# Connectors_GPIOs.net
KiCad netlist of a schematic drawn in Altium Designer
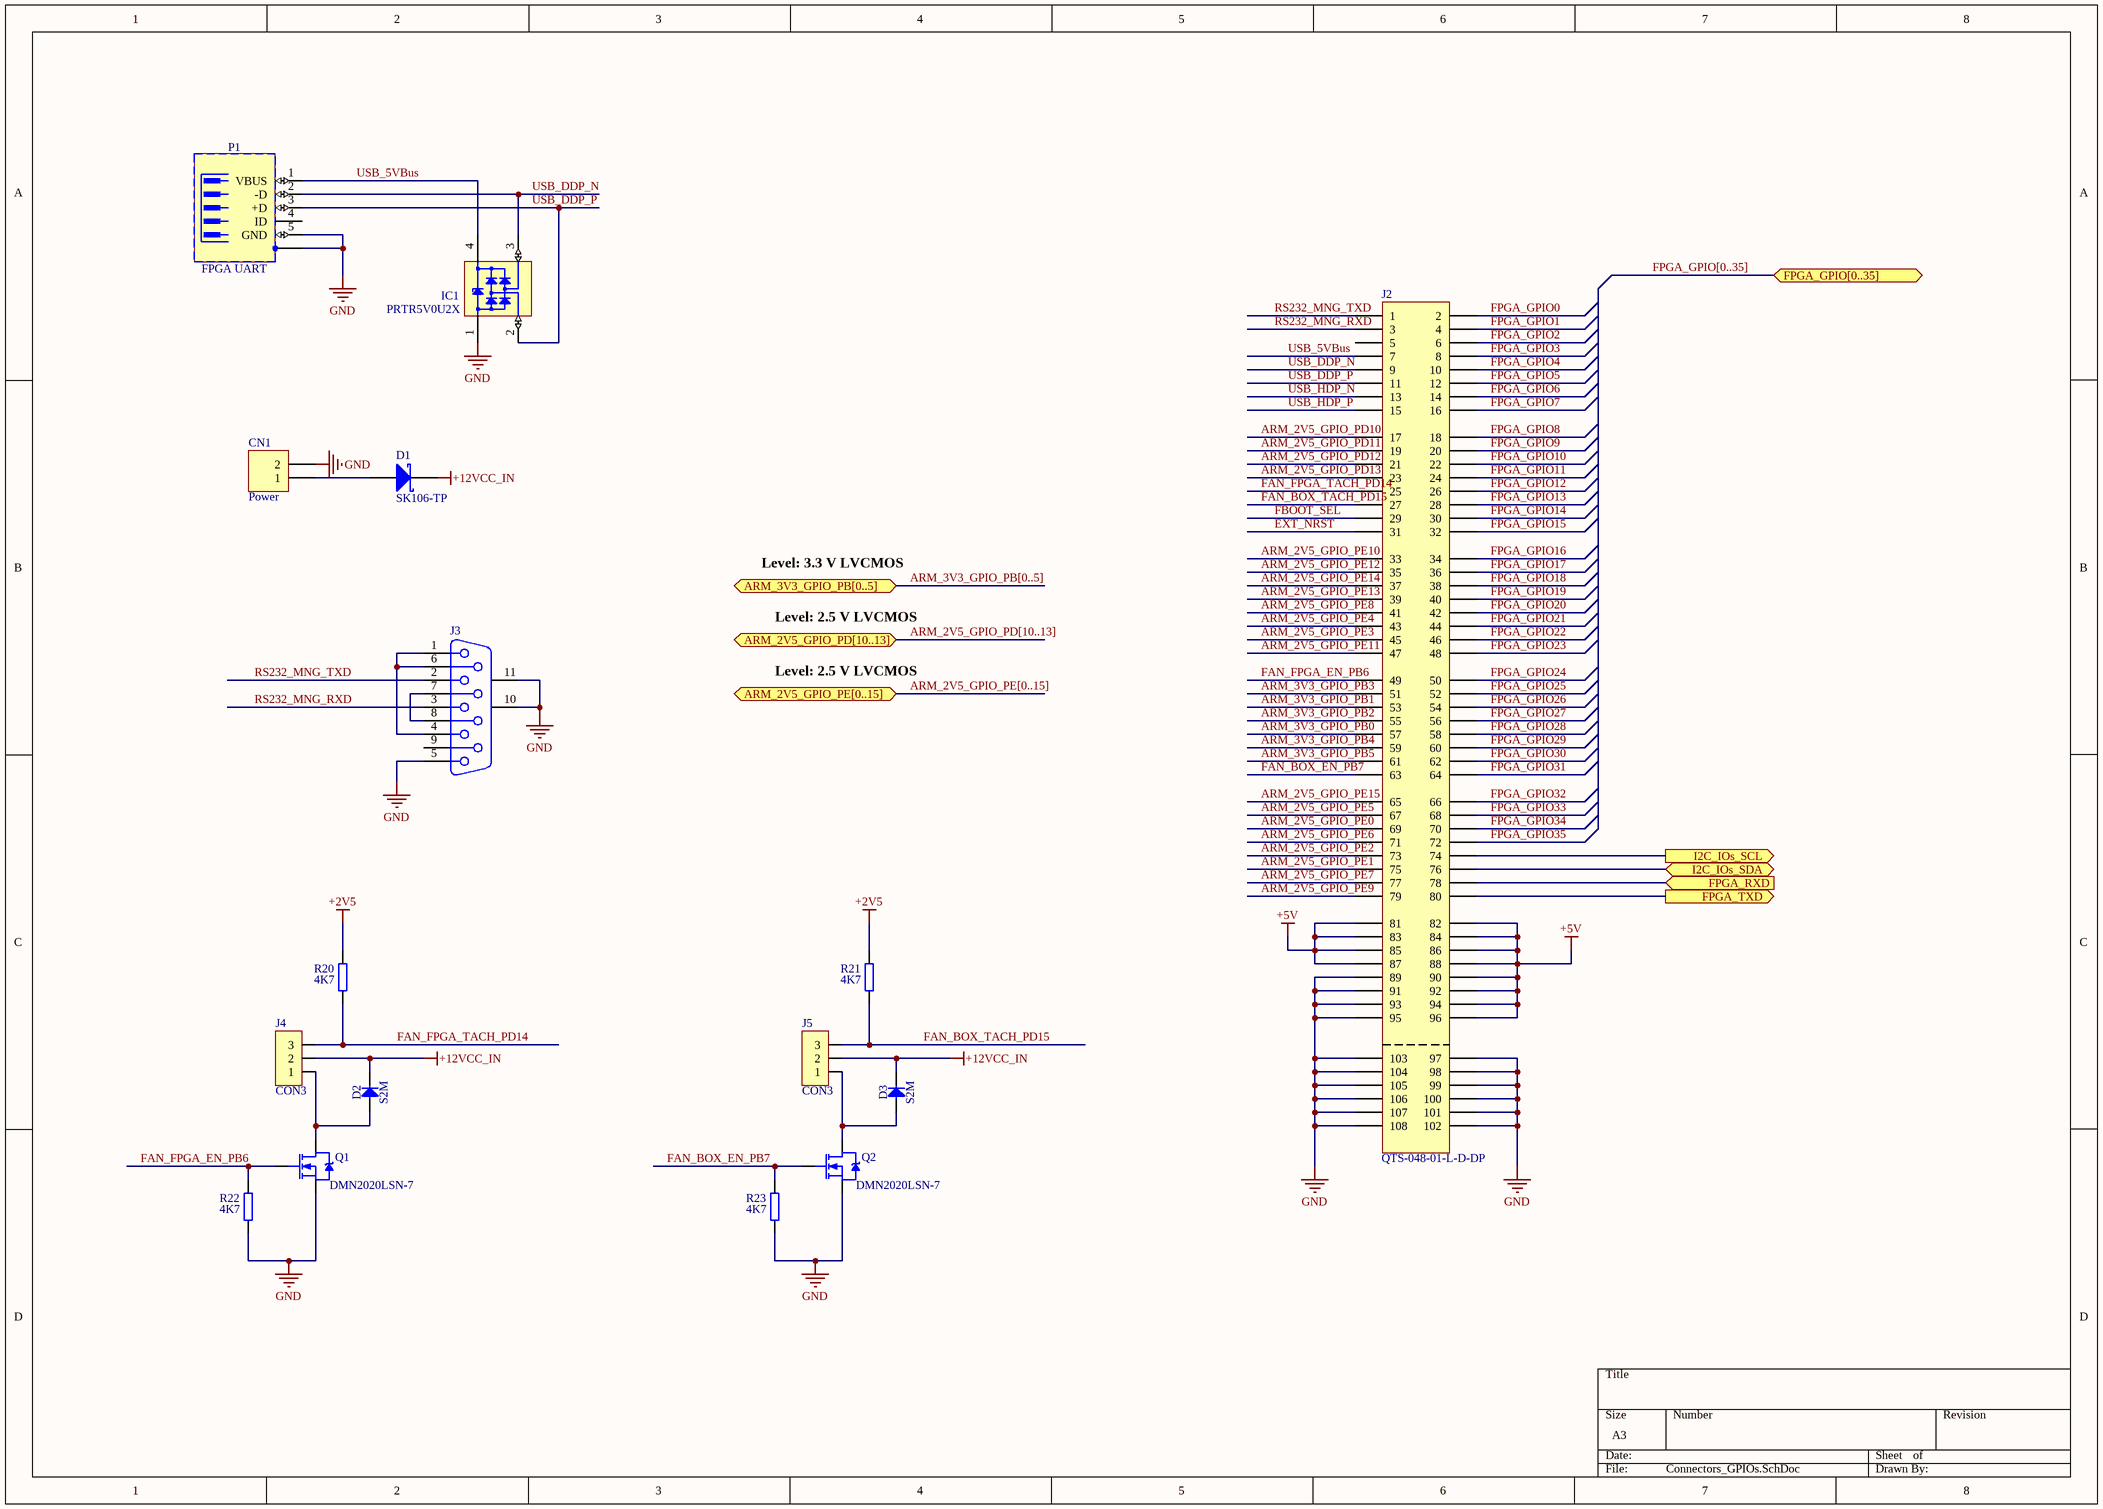
[diagram p0: Connectors_GPIOs.SchDoc]

(export (version "E")
  (design (tool "Eeschema 10.0.6"))
  (components
    (comp (ref "CN1")
      (value "Power")
      (description "Header, 2-Pin")
      (fields (field (name "PUBLISHER") "Altium Limited"))
      (libsource (lib "Miscellaneous Connectors") (part "Header 2"))
    )
    (comp (ref "D1")
      (value "SK106-TP")
      (footprint "DIOM7959X262N")
      (description "Schottky Diode 10A 60V")
      (libsource (lib "wr_switch") (part "SK106-TP"))
    )
    (comp (ref "D2")
      (value "S2M")
      (footprint "DIOM5336X265N")
      (description "Diode")
      (fields
        (field (name "VOLTAGE") "1000V")
        (field (name "POWER") "2A")
        (field (name "AUTHOR") "CERN DEM JLC")
      )
      (libsource (lib "ICs And Semiconductors") (part "Diode"))
    )
    (comp (ref "D3")
      (value "S2M")
      (footprint "DIOM5336X265N")
      (description "Diode")
      (fields
        (field (name "VOLTAGE") "1000V")
        (field (name "POWER") "2A")
        (field (name "AUTHOR") "CERN DEM JLC")
      )
      (libsource (lib "ICs And Semiconductors") (part "Diode"))
    )
    (comp (ref "IC1")
      (value "PRTR5V0U2X")
      (footprint "SOT190P230X110-4N")
      (description "Ultra Low Capacitance Double Rail-to-Rail ESD Protection Diode")
      (fields
        (field (name "VOLTAGE") "5.5V")
        (field (name "MANUFACTURER") "PHILIPS NXP")
        (field (name "AUTHOR") "CERN DEM JLC")
      )
      (libsource (lib "wr_switch") (part "PRTR5V0U2X"))
    )
    (comp (ref "J2")
      (value "QTS-048-01-L-D-DP")
      (footprint "QTS-048-XX-X-D-DP-A")
      (description "High Speed Ground Plane Header")
      (libsource (lib "wr_switch") (part "QTS-048-01-L-D-DP"))
    )
    (comp (ref "J3")
      (value "D Connector 9")
      (footprint "DSUB1.385-2H9")
      (description "Receptacle Assembly, 9 Position, Right Angle")
      (fields (field (name "PUBLISHER") "Altium Limited"))
      (libsource (lib "Miscellaneous Connectors") (part "D Connector 9"))
    )
    (comp (ref "J4")
      (value "CON3")
      (footprint "HDR1X3")
      (description "Connector")
      (libsource (lib "LIBRARY_SCH") (part "CON3"))
    )
    (comp (ref "J5")
      (value "CON3")
      (footprint "HDR1X3")
      (description "Connector")
      (libsource (lib "LIBRARY_SCH") (part "CON3"))
    )
    (comp (ref "P1")
      (value "FPGA UART")
      (footprint "TYCO_1734035-1")
      (description "5 Pin + 1 Shield USB Receptacle")
      (fields
        (field (name "PART NUMBER") "TYCO_1734035-1")
        (field (name "MANUFACTURER") "TYCO ELECTRONICS")
        (field (name "AUTHOR") "CERN DEM JLC")
      )
      (libsource (lib "Connectors") (part "Connector USB 5 Pin + 1Shield"))
    )
    (comp (ref "Q1")
      (value "DMN2020LSN-7")
      (footprint "SC-59-3")
      (description "N-Channel Power MOSFET")
      (fields (field (name "MANUFACTURER") "Diodes Inc.") (field (name "PUBLISHER") "Altium Limited"))
      (libsource (lib "wr_switch") (part "NMOS-2"))
    )
    (comp (ref "Q2")
      (value "DMN2020LSN-7")
      (footprint "SC-59-3")
      (description "N-Channel Power MOSFET")
      (fields (field (name "MANUFACTURER") "Diodes Inc.") (field (name "PUBLISHER") "Altium Limited"))
      (libsource (lib "wr_switch") (part "NMOS-2"))
    )
    (comp (ref "R20")
      (value "4K7")
      (footprint "0603")
      (description "SMD Resistor")
      (fields (field (name "TOLERANCE") "±1%"))
      (libsource (lib "wr_switch") (part "RES_SMD"))
    )
    (comp (ref "R21")
      (value "4K7")
      (footprint "0603")
      (description "SMD Resistor")
      (fields (field (name "TOLERANCE") "±1%"))
      (libsource (lib "wr_switch") (part "RES_SMD"))
    )
    (comp (ref "R22")
      (value "4K7")
      (footprint "0603")
      (description "SMD Resistor")
      (fields (field (name "TOLERANCE") "±1%"))
      (libsource (lib "wr_switch") (part "RES_SMD"))
    )
    (comp (ref "R23")
      (value "4K7")
      (footprint "0603")
      (description "SMD Resistor")
      (fields (field (name "TOLERANCE") "±1%"))
      (libsource (lib "wr_switch") (part "RES_SMD"))
    )
  )
  (nets
    (net (code "1") (name "+2V5") (class "Default")
      (node (ref "R20") (pin "1") (pinfunction "1_1") (pintype "passive"))
      (node (ref "R21") (pin "1") (pinfunction "1_1") (pintype "passive"))
    )
    (net (code "2") (name "+5V") (class "Default")
      (node (ref "J2") (pin "81") (pinfunction "81_81") (pintype "passive"))
      (node (ref "J2") (pin "82") (pinfunction "82_82") (pintype "passive"))
      (node (ref "J2") (pin "83") (pinfunction "83_83") (pintype "passive"))
      (node (ref "J2") (pin "84") (pinfunction "84_84") (pintype "passive"))
      (node (ref "J2") (pin "85") (pinfunction "85_85") (pintype "passive"))
      (node (ref "J2") (pin "86") (pinfunction "86_86") (pintype "passive"))
      (node (ref "J2") (pin "87") (pinfunction "87_87") (pintype "passive"))
      (node (ref "J2") (pin "88") (pinfunction "88_88") (pintype "passive"))
      (node (ref "J2") (pin "90") (pinfunction "90_90") (pintype "passive"))
      (node (ref "J2") (pin "92") (pinfunction "92_92") (pintype "passive"))
      (node (ref "J2") (pin "94") (pinfunction "94_94") (pintype "passive"))
      (node (ref "J2") (pin "96") (pinfunction "96_96") (pintype "passive"))
    )
    (net (code "3") (name "+12VCC_IN") (class "Default")
      (node (ref "D1") (pin "2") (pinfunction "K_2") (pintype "passive"))
      (node (ref "D2") (pin "1") (pinfunction "C_1") (pintype "passive"))
      (node (ref "D3") (pin "1") (pinfunction "C_1") (pintype "passive"))
      (node (ref "J4") (pin "2") (pinfunction "2_2") (pintype "passive"))
      (node (ref "J5") (pin "2") (pinfunction "2_2") (pintype "passive"))
    )
    (net (code "4") (name "/ARM_2V5_GPIO_PD10") (class "Default")
      (node (ref "J2") (pin "17") (pinfunction "17_17") (pintype "passive"))
    )
    (net (code "5") (name "/ARM_2V5_GPIO_PD11") (class "Default")
      (node (ref "J2") (pin "19") (pinfunction "19_19") (pintype "passive"))
    )
    (net (code "6") (name "/ARM_2V5_GPIO_PD12") (class "Default")
      (node (ref "J2") (pin "21") (pinfunction "21_21") (pintype "passive"))
    )
    (net (code "7") (name "/ARM_2V5_GPIO_PD13") (class "Default")
      (node (ref "J2") (pin "23") (pinfunction "23_23") (pintype "passive"))
    )
    (net (code "9") (name "/ARM_2V5_GPIO_PE0") (class "Default")
      (node (ref "J2") (pin "69") (pinfunction "69_69") (pintype "passive"))
    )
    (net (code "10") (name "/ARM_2V5_GPIO_PE1") (class "Default")
      (node (ref "J2") (pin "75") (pinfunction "75_75") (pintype "passive"))
    )
    (net (code "11") (name "/ARM_2V5_GPIO_PE2") (class "Default")
      (node (ref "J2") (pin "73") (pinfunction "73_73") (pintype "passive"))
    )
    (net (code "12") (name "/ARM_2V5_GPIO_PE3") (class "Default")
      (node (ref "J2") (pin "45") (pinfunction "45_45") (pintype "passive"))
    )
    (net (code "13") (name "/ARM_2V5_GPIO_PE4") (class "Default")
      (node (ref "J2") (pin "43") (pinfunction "43_43") (pintype "passive"))
    )
    (net (code "14") (name "/ARM_2V5_GPIO_PE5") (class "Default")
      (node (ref "J2") (pin "67") (pinfunction "67_67") (pintype "passive"))
    )
    (net (code "15") (name "/ARM_2V5_GPIO_PE6") (class "Default")
      (node (ref "J2") (pin "71") (pinfunction "71_71") (pintype "passive"))
    )
    (net (code "16") (name "/ARM_2V5_GPIO_PE7") (class "Default")
      (node (ref "J2") (pin "77") (pinfunction "77_77") (pintype "passive"))
    )
    (net (code "17") (name "/ARM_2V5_GPIO_PE8") (class "Default")
      (node (ref "J2") (pin "41") (pinfunction "41_41") (pintype "passive"))
    )
    (net (code "18") (name "/ARM_2V5_GPIO_PE9") (class "Default")
      (node (ref "J2") (pin "79") (pinfunction "79_79") (pintype "passive"))
    )
    (net (code "19") (name "/ARM_2V5_GPIO_PE10") (class "Default")
      (node (ref "J2") (pin "33") (pinfunction "33_33") (pintype "passive"))
    )
    (net (code "20") (name "/ARM_2V5_GPIO_PE11") (class "Default")
      (node (ref "J2") (pin "47") (pinfunction "47_47") (pintype "passive"))
    )
    (net (code "21") (name "/ARM_2V5_GPIO_PE12") (class "Default")
      (node (ref "J2") (pin "35") (pinfunction "35_35") (pintype "passive"))
    )
    (net (code "22") (name "/ARM_2V5_GPIO_PE13") (class "Default")
      (node (ref "J2") (pin "39") (pinfunction "39_39") (pintype "passive"))
    )
    (net (code "23") (name "/ARM_2V5_GPIO_PE14") (class "Default")
      (node (ref "J2") (pin "37") (pinfunction "37_37") (pintype "passive"))
    )
    (net (code "24") (name "/ARM_2V5_GPIO_PE15") (class "Default")
      (node (ref "J2") (pin "65") (pinfunction "65_65") (pintype "passive"))
    )
    (net (code "26") (name "/ARM_3V3_GPIO_PB0") (class "Default")
      (node (ref "J2") (pin "57") (pinfunction "57_57") (pintype "passive"))
    )
    (net (code "27") (name "/ARM_3V3_GPIO_PB1") (class "Default")
      (node (ref "J2") (pin "53") (pinfunction "53_53") (pintype "passive"))
    )
    (net (code "28") (name "/ARM_3V3_GPIO_PB2") (class "Default")
      (node (ref "J2") (pin "55") (pinfunction "55_55") (pintype "passive"))
    )
    (net (code "29") (name "/ARM_3V3_GPIO_PB3") (class "Default")
      (node (ref "J2") (pin "51") (pinfunction "51_51") (pintype "passive"))
    )
    (net (code "30") (name "/ARM_3V3_GPIO_PB4") (class "Default")
      (node (ref "J2") (pin "59") (pinfunction "59_59") (pintype "passive"))
    )
    (net (code "31") (name "/ARM_3V3_GPIO_PB5") (class "Default")
      (node (ref "J2") (pin "61") (pinfunction "61_61") (pintype "passive"))
    )
    (net (code "33") (name "/EXT_NRST") (class "Default")
      (node (ref "J2") (pin "31") (pinfunction "31_31") (pintype "passive"))
    )
    (net (code "34") (name "/FAN_BOX_EN_PB7") (class "Default")
      (node (ref "J2") (pin "63") (pinfunction "63_63") (pintype "passive"))
      (node (ref "Q2") (pin "1") (pinfunction "G_1") (pintype "passive"))
      (node (ref "R23") (pin "1") (pinfunction "1_1") (pintype "passive"))
    )
    (net (code "35") (name "/FAN_BOX_TACH_PD15") (class "Default")
      (node (ref "J2") (pin "27") (pinfunction "27_27") (pintype "passive"))
      (node (ref "J5") (pin "3") (pinfunction "3_3") (pintype "passive"))
      (node (ref "R21") (pin "2") (pinfunction "2_2") (pintype "passive"))
    )
    (net (code "36") (name "/FAN_FPGA_EN_PB6") (class "Default")
      (node (ref "J2") (pin "49") (pinfunction "49_49") (pintype "passive"))
      (node (ref "Q1") (pin "1") (pinfunction "G_1") (pintype "passive"))
      (node (ref "R22") (pin "1") (pinfunction "1_1") (pintype "passive"))
    )
    (net (code "37") (name "/FAN_FPGA_TACH_PD14") (class "Default")
      (node (ref "J2") (pin "25") (pinfunction "25_25") (pintype "passive"))
      (node (ref "J4") (pin "3") (pinfunction "3_3") (pintype "passive"))
      (node (ref "R20") (pin "2") (pinfunction "2_2") (pintype "passive"))
    )
    (net (code "38") (name "/FBOOT_SEL") (class "Default")
      (node (ref "J2") (pin "29") (pinfunction "29_29") (pintype "passive"))
    )
    (net (code "39") (name "/FPGA_GPIO0") (class "Default")
      (node (ref "J2") (pin "2") (pinfunction "2_2") (pintype "passive"))
    )
    (net (code "40") (name "/FPGA_GPIO1") (class "Default")
      (node (ref "J2") (pin "4") (pinfunction "4_4") (pintype "passive"))
    )
    (net (code "41") (name "/FPGA_GPIO2") (class "Default")
      (node (ref "J2") (pin "6") (pinfunction "6_6") (pintype "passive"))
    )
    (net (code "42") (name "/FPGA_GPIO3") (class "Default")
      (node (ref "J2") (pin "8") (pinfunction "8_8") (pintype "passive"))
    )
    (net (code "43") (name "/FPGA_GPIO4") (class "Default")
      (node (ref "J2") (pin "10") (pinfunction "10_10") (pintype "passive"))
    )
    (net (code "44") (name "/FPGA_GPIO5") (class "Default")
      (node (ref "J2") (pin "12") (pinfunction "12_12") (pintype "passive"))
    )
    (net (code "45") (name "/FPGA_GPIO6") (class "Default")
      (node (ref "J2") (pin "14") (pinfunction "14_14") (pintype "passive"))
    )
    (net (code "46") (name "/FPGA_GPIO7") (class "Default")
      (node (ref "J2") (pin "16") (pinfunction "16_16") (pintype "passive"))
    )
    (net (code "47") (name "/FPGA_GPIO8") (class "Default")
      (node (ref "J2") (pin "18") (pinfunction "18_18") (pintype "passive"))
    )
    (net (code "48") (name "/FPGA_GPIO9") (class "Default")
      (node (ref "J2") (pin "20") (pinfunction "20_20") (pintype "passive"))
    )
    (net (code "49") (name "/FPGA_GPIO10") (class "Default")
      (node (ref "J2") (pin "22") (pinfunction "22_22") (pintype "passive"))
    )
    (net (code "50") (name "/FPGA_GPIO11") (class "Default")
      (node (ref "J2") (pin "24") (pinfunction "24_24") (pintype "passive"))
    )
    (net (code "51") (name "/FPGA_GPIO12") (class "Default")
      (node (ref "J2") (pin "26") (pinfunction "26_26") (pintype "passive"))
    )
    (net (code "52") (name "/FPGA_GPIO13") (class "Default")
      (node (ref "J2") (pin "28") (pinfunction "28_28") (pintype "passive"))
    )
    (net (code "53") (name "/FPGA_GPIO14") (class "Default")
      (node (ref "J2") (pin "30") (pinfunction "30_30") (pintype "passive"))
    )
    (net (code "54") (name "/FPGA_GPIO15") (class "Default")
      (node (ref "J2") (pin "32") (pinfunction "32_32") (pintype "passive"))
    )
    (net (code "55") (name "/FPGA_GPIO16") (class "Default")
      (node (ref "J2") (pin "34") (pinfunction "34_34") (pintype "passive"))
    )
    (net (code "56") (name "/FPGA_GPIO17") (class "Default")
      (node (ref "J2") (pin "36") (pinfunction "36_36") (pintype "passive"))
    )
    (net (code "57") (name "/FPGA_GPIO18") (class "Default")
      (node (ref "J2") (pin "38") (pinfunction "38_38") (pintype "passive"))
    )
    (net (code "58") (name "/FPGA_GPIO19") (class "Default")
      (node (ref "J2") (pin "40") (pinfunction "40_40") (pintype "passive"))
    )
    (net (code "59") (name "/FPGA_GPIO20") (class "Default")
      (node (ref "J2") (pin "42") (pinfunction "42_42") (pintype "passive"))
    )
    (net (code "60") (name "/FPGA_GPIO21") (class "Default")
      (node (ref "J2") (pin "44") (pinfunction "44_44") (pintype "passive"))
    )
    (net (code "61") (name "/FPGA_GPIO22") (class "Default")
      (node (ref "J2") (pin "46") (pinfunction "46_46") (pintype "passive"))
    )
    (net (code "62") (name "/FPGA_GPIO23") (class "Default")
      (node (ref "J2") (pin "48") (pinfunction "48_48") (pintype "passive"))
    )
    (net (code "63") (name "/FPGA_GPIO24") (class "Default")
      (node (ref "J2") (pin "50") (pinfunction "50_50") (pintype "passive"))
    )
    (net (code "64") (name "/FPGA_GPIO25") (class "Default")
      (node (ref "J2") (pin "52") (pinfunction "52_52") (pintype "passive"))
    )
    (net (code "65") (name "/FPGA_GPIO26") (class "Default")
      (node (ref "J2") (pin "54") (pinfunction "54_54") (pintype "passive"))
    )
    (net (code "66") (name "/FPGA_GPIO27") (class "Default")
      (node (ref "J2") (pin "56") (pinfunction "56_56") (pintype "passive"))
    )
    (net (code "67") (name "/FPGA_GPIO28") (class "Default")
      (node (ref "J2") (pin "58") (pinfunction "58_58") (pintype "passive"))
    )
    (net (code "68") (name "/FPGA_GPIO29") (class "Default")
      (node (ref "J2") (pin "60") (pinfunction "60_60") (pintype "passive"))
    )
    (net (code "69") (name "/FPGA_GPIO30") (class "Default")
      (node (ref "J2") (pin "62") (pinfunction "62_62") (pintype "passive"))
    )
    (net (code "70") (name "/FPGA_GPIO31") (class "Default")
      (node (ref "J2") (pin "64") (pinfunction "64_64") (pintype "passive"))
    )
    (net (code "71") (name "/FPGA_GPIO32") (class "Default")
      (node (ref "J2") (pin "66") (pinfunction "66_66") (pintype "passive"))
    )
    (net (code "72") (name "/FPGA_GPIO33") (class "Default")
      (node (ref "J2") (pin "68") (pinfunction "68_68") (pintype "passive"))
    )
    (net (code "73") (name "/FPGA_GPIO34") (class "Default")
      (node (ref "J2") (pin "70") (pinfunction "70_70") (pintype "passive"))
    )
    (net (code "74") (name "/FPGA_GPIO35") (class "Default")
      (node (ref "J2") (pin "72") (pinfunction "72_72") (pintype "passive"))
    )
    (net (code "76") (name "/FPGA_RXD") (class "Default")
      (node (ref "J2") (pin "78") (pinfunction "78_78") (pintype "passive"))
    )
    (net (code "77") (name "/FPGA_TXD") (class "Default")
      (node (ref "J2") (pin "80") (pinfunction "80_80") (pintype "passive"))
    )
    (net (code "78") (name "/I2C_IOs_SCL") (class "Default")
      (node (ref "J2") (pin "74") (pinfunction "74_74") (pintype "passive"))
    )
    (net (code "79") (name "/I2C_IOs_SDA") (class "Default")
      (node (ref "J2") (pin "76") (pinfunction "76_76") (pintype "passive"))
    )
    (net (code "80") (name "/RS232_MNG_RXD") (class "Default")
      (node (ref "J2") (pin "3") (pinfunction "3_3") (pintype "passive"))
      (node (ref "J3") (pin "3") (pinfunction "3_3") (pintype "passive"))
    )
    (net (code "81") (name "/RS232_MNG_TXD") (class "Default")
      (node (ref "J2") (pin "1") (pinfunction "1_1") (pintype "passive"))
      (node (ref "J3") (pin "2") (pinfunction "2_2") (pintype "passive"))
    )
    (net (code "82") (name "/USB_5VBus") (class "Default")
      (node (ref "IC1") (pin "4") (pinfunction "VCC_4") (pintype "power_in"))
      (node (ref "J2") (pin "7") (pinfunction "7_7") (pintype "passive"))
      (node (ref "P1") (pin "1") (pinfunction "VBUS_1") (pintype "bidirectional"))
    )
    (net (code "83") (name "/USB_DDP_N") (class "Default")
      (node (ref "IC1") (pin "3") (pinfunction "I/O2_3") (pintype "bidirectional"))
      (node (ref "J2") (pin "9") (pinfunction "9_9") (pintype "passive"))
      (node (ref "P1") (pin "2") (pinfunction "-D_2") (pintype "bidirectional"))
    )
    (net (code "84") (name "/USB_DDP_P") (class "Default")
      (node (ref "IC1") (pin "2") (pinfunction "I/O1_2") (pintype "bidirectional"))
      (node (ref "J2") (pin "11") (pinfunction "11_11") (pintype "passive"))
      (node (ref "P1") (pin "3") (pinfunction "+D_3") (pintype "bidirectional"))
    )
    (net (code "85") (name "/USB_HDP_N") (class "Default")
      (node (ref "J2") (pin "13") (pinfunction "13_13") (pintype "passive"))
    )
    (net (code "86") (name "/USB_HDP_P") (class "Default")
      (node (ref "J2") (pin "15") (pinfunction "15_15") (pintype "passive"))
    )
    (net (code "87") (name "GND") (class "Default")
      (node (ref "CN1") (pin "2") (pinfunction "2_2") (pintype "passive"))
      (node (ref "IC1") (pin "1") (pinfunction "GND_1") (pintype "power_in"))
      (node (ref "J2") (pin "100") (pinfunction "100_100") (pintype "passive"))
      (node (ref "J2") (pin "101") (pinfunction "101_101") (pintype "passive"))
      (node (ref "J2") (pin "102") (pinfunction "102_102") (pintype "passive"))
      (node (ref "J2") (pin "103") (pinfunction "103_103") (pintype "passive"))
      (node (ref "J2") (pin "104") (pinfunction "104_104") (pintype "passive"))
      (node (ref "J2") (pin "105") (pinfunction "105_105") (pintype "passive"))
      (node (ref "J2") (pin "106") (pinfunction "106_106") (pintype "passive"))
      (node (ref "J2") (pin "107") (pinfunction "107_107") (pintype "passive"))
      (node (ref "J2") (pin "108") (pinfunction "108_108") (pintype "passive"))
      (node (ref "J2") (pin "89") (pinfunction "89_89") (pintype "passive"))
      (node (ref "J2") (pin "91") (pinfunction "91_91") (pintype "passive"))
      (node (ref "J2") (pin "93") (pinfunction "93_93") (pintype "passive"))
      (node (ref "J2") (pin "95") (pinfunction "95_95") (pintype "passive"))
      (node (ref "J2") (pin "97") (pinfunction "97_97") (pintype "passive"))
      (node (ref "J2") (pin "98") (pinfunction "98_98") (pintype "passive"))
      (node (ref "J2") (pin "99") (pinfunction "99_99") (pintype "passive"))
      (node (ref "J3") (pin "10") (pinfunction "MH1_10") (pintype "passive"))
      (node (ref "J3") (pin "11") (pinfunction "MH2_11") (pintype "passive"))
      (node (ref "J3") (pin "5") (pinfunction "5_5") (pintype "passive"))
      (node (ref "P1") (pin "5") (pinfunction "GND_5") (pintype "bidirectional"))
      (node (ref "P1") (pin "6") (pinfunction "SH_6") (pintype "power_in"))
      (node (ref "Q1") (pin "3") (pinfunction "S_3") (pintype "passive"))
      (node (ref "Q2") (pin "3") (pinfunction "S_3") (pintype "passive"))
      (node (ref "R22") (pin "2") (pinfunction "2_2") (pintype "passive"))
      (node (ref "R23") (pin "2") (pinfunction "2_2") (pintype "passive"))
    )
    (net (code "88") (name "Net-(D1-A)") (class "Default")
      (node (ref "CN1") (pin "1") (pinfunction "1_1") (pintype "passive"))
      (node (ref "D1") (pin "1") (pinfunction "A_1") (pintype "passive"))
    )
    (net (code "89") (name "Net-(D2-A)") (class "Default")
      (node (ref "D2") (pin "2") (pinfunction "A_2") (pintype "passive"))
      (node (ref "J4") (pin "1") (pinfunction "1_1") (pintype "passive"))
      (node (ref "Q1") (pin "2") (pinfunction "D_2") (pintype "passive"))
    )
    (net (code "90") (name "Net-(D3-A)") (class "Default")
      (node (ref "D3") (pin "2") (pinfunction "A_2") (pintype "passive"))
      (node (ref "J5") (pin "1") (pinfunction "1_1") (pintype "passive"))
      (node (ref "Q2") (pin "2") (pinfunction "D_2") (pintype "passive"))
    )
    (net (code "91") (name "Net-(J3-Pad1)") (class "Default")
      (node (ref "J3") (pin "1") (pinfunction "1_1") (pintype "passive"))
      (node (ref "J3") (pin "4") (pinfunction "4_4") (pintype "passive"))
      (node (ref "J3") (pin "6") (pinfunction "6_6") (pintype "passive"))
    )
    (net (code "92") (name "Net-(J3-Pad7)") (class "Default")
      (node (ref "J3") (pin "7") (pinfunction "7_7") (pintype "passive"))
      (node (ref "J3") (pin "8") (pinfunction "8_8") (pintype "passive"))
    )
    (net (code "93") (name "unconnected-(J2-Pad5)") (class "Default")
      (node (ref "J2") (pin "5") (pinfunction "5_5") (pintype "passive"))
    )
    (net (code "94") (name "unconnected-(J3-Pad9)") (class "Default")
      (node (ref "J3") (pin "9") (pinfunction "9_9") (pintype "passive"))
    )
    (net (code "95") (name "unconnected-(P1-ID-Pad4)") (class "Default")
      (node (ref "P1") (pin "4") (pinfunction "ID_4") (pintype "passive"))
    )
  )
)
